# 261003902xxxx-HW-V1_1.net
KiCad netlist of a schematic drawn in EAGLE
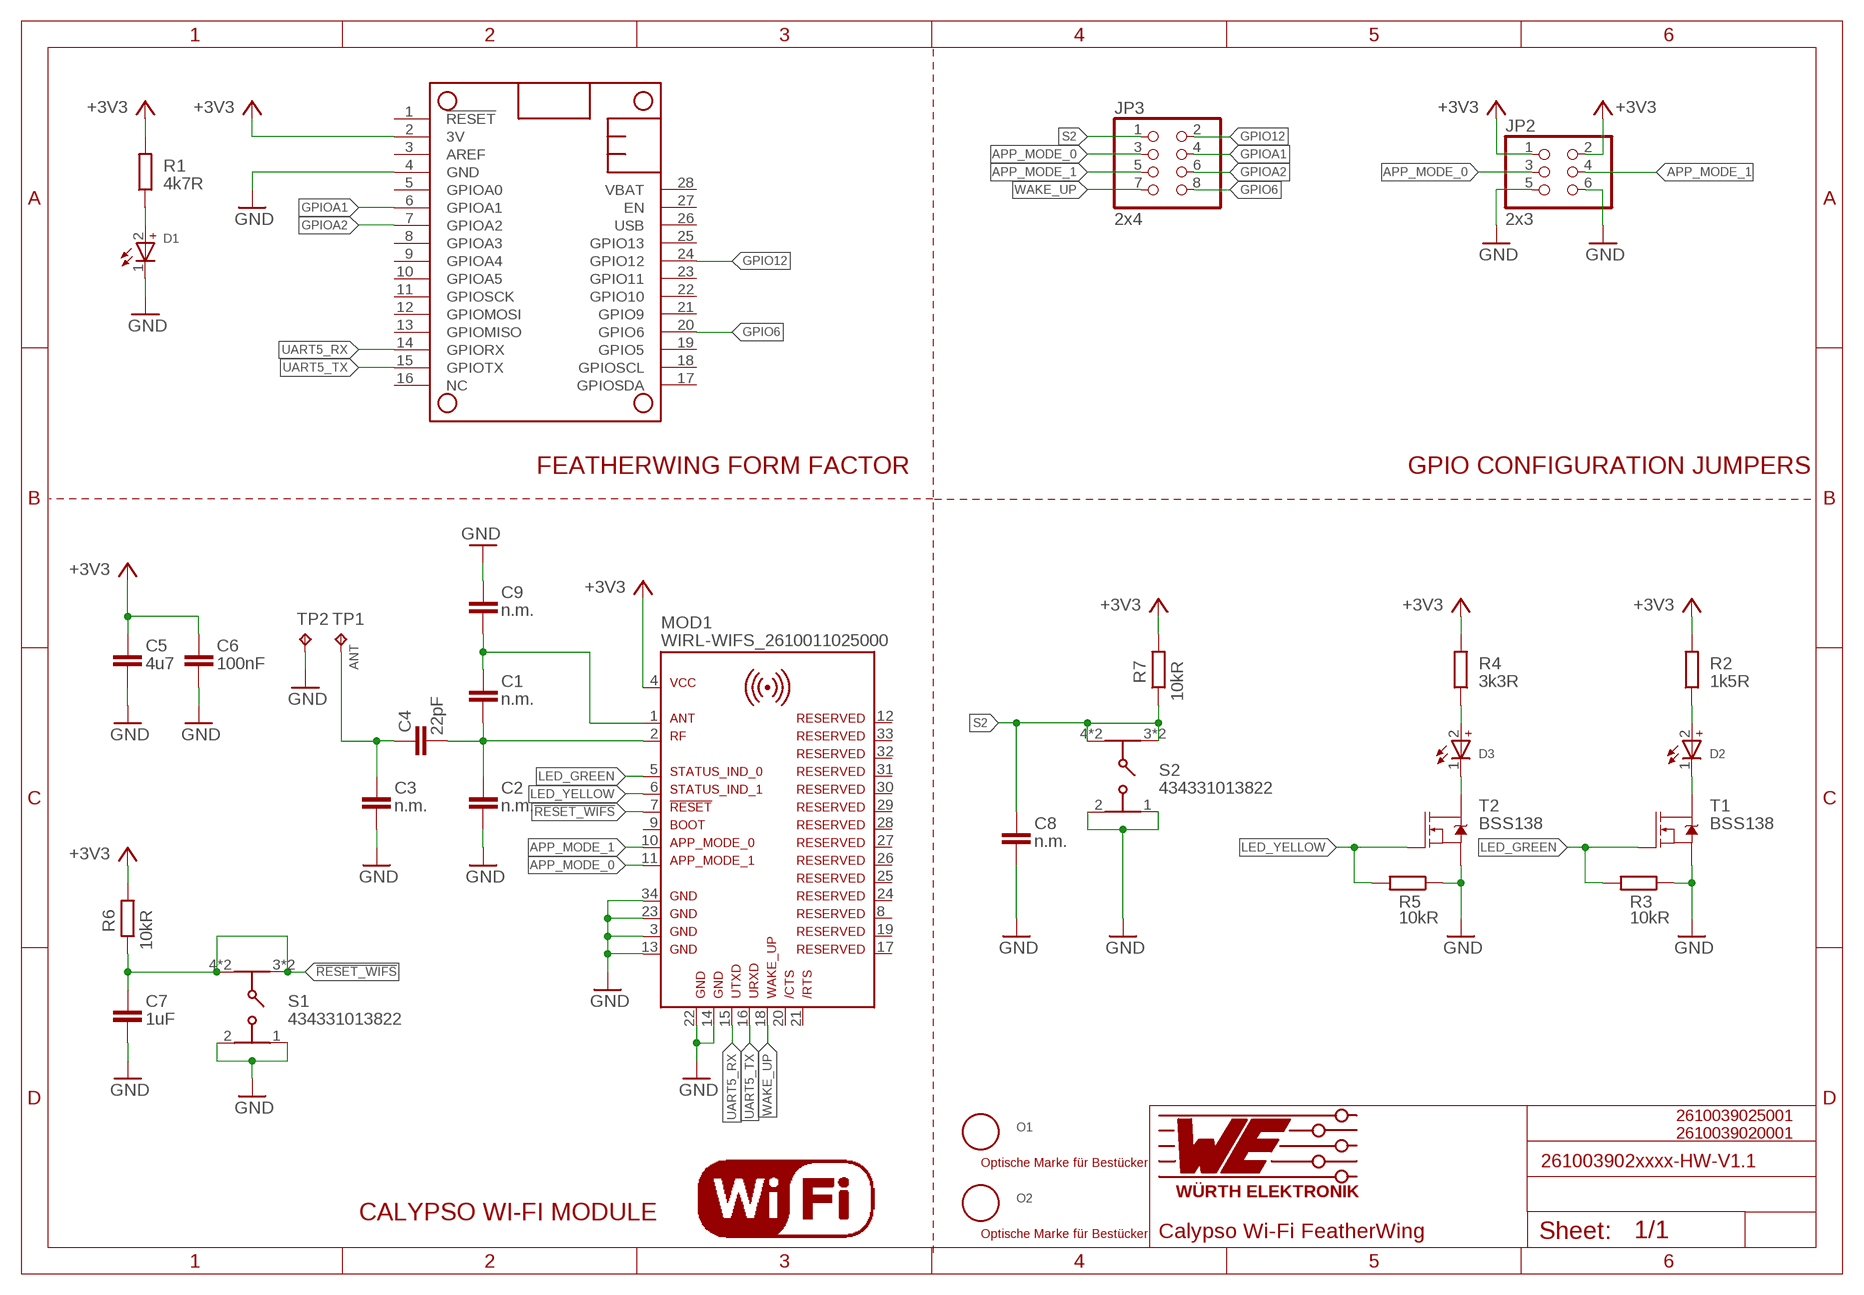
[diagram p0: schematic, sheet 1]

(export (version "E")
  (design (tool "Eeschema 10.0.6"))
  (components
    (comp (ref "C1")
      (value "n.m.")
      (footprint "eagle-import:C0402_IPC")
      (libsource (lib "eagle-import") (part "rcl-amber_C0402_IPC"))
    )
    (comp (ref "C2")
      (value "n.m.")
      (footprint "eagle-import:C0201_IPC")
      (libsource (lib "eagle-import") (part "rcl-amber_C0201_IPC"))
    )
    (comp (ref "C3")
      (value "n.m.")
      (footprint "eagle-import:C0201_IPC")
      (libsource (lib "eagle-import") (part "rcl-amber_C0201_IPC"))
    )
    (comp (ref "C4")
      (value "22pF")
      (footprint "eagle-import:C0402_IPC")
      (fields (field (name "MANUFACTURER") "Samsung"))
      (libsource (lib "eagle-import") (part "rcl-amber_C0402_IPC22PF"))
    )
    (comp (ref "C5")
      (value "4u7")
      (footprint "eagle-import:C0402_IPC")
      (fields (field (name "MANUFACTURER") "Würth Elektronik"))
      (libsource (lib "eagle-import") (part "C0402_IPC4.7UF"))
    )
    (comp (ref "C6")
      (value "100nF")
      (footprint "eagle-import:C0402_IPC")
      (fields (field (name "MANUFACTURER") "Yageo"))
      (libsource (lib "eagle-import") (part "rcl-amber_C0402_IPC100NF"))
    )
    (comp (ref "C7")
      (value "1uF")
      (footprint "eagle-import:C0402_IPC")
      (fields (field (name "MANUFACTURER") "Samsung"))
      (libsource (lib "eagle-import") (part "rcl-amber_C0402_IPC1UF"))
    )
    (comp (ref "C8")
      (value "n.m.")
      (footprint "eagle-import:C0402_IPC")
      (libsource (lib "eagle-import") (part "rcl-amber_C0402_IPC"))
    )
    (comp (ref "C9")
      (value "n.m.")
      (footprint "eagle-import:C0201_IPC")
      (libsource (lib "eagle-import") (part "rcl-amber_C0201_IPC"))
    )
    (comp (ref "D1")
      (value "RED")
      (footprint "eagle-import:WL-SMSW_1204_A")
      (fields (field (name "MANUFACTURER") "Würth Elektronik"))
      (libsource (lib "eagle-import") (part "WL-SMSW_1204_155124RS73200"))
    )
    (comp (ref "D2")
      (value "GREEN")
      (footprint "eagle-import:WL-SMSW_1204_A")
      (fields (field (name "MANUFACTURER") "Würth Elektronik"))
      (libsource (lib "eagle-import") (part "WL-SMSW_1204_155124VS73200"))
    )
    (comp (ref "D3")
      (value "YELLOW")
      (footprint "eagle-import:WL-SMSW_1204_A")
      (fields (field (name "MANUFACTURER") "Würth Elektronik"))
      (libsource (lib "eagle-import") (part "WL-SMSW_1204_155124YS73200"))
    )
    (comp (ref "JP2")
      (value "2x3")
      (footprint "eagle-import:2X03")
      (fields (field (name "MANUFACTURER") "Würth Elektronik"))
      (libsource (lib "eagle-import") (part "PINHD-2X3"))
    )
    (comp (ref "JP3")
      (value "2x4")
      (footprint "eagle-import:2X04")
      (fields (field (name "MANUFACTURER") "Würth Elektronik"))
      (libsource (lib "eagle-import") (part "PINHD-2X4"))
    )
    (comp (ref "MOD1")
      (value "WIRL-WIFS_2610011025000")
      (footprint "eagle-import:WIRL-WIFS_2610011025000")
      (fields (field (name "MANUFACTURER") "Würth Elektronik"))
      (libsource (lib "eagle-import") (part "WIRL-WIFS_2610011025000"))
    )
    (comp (ref "MS1")
      (value "header: 1 x 12 & 1 x 16")
      (footprint "eagle-import:FEATHERWING_80MM")
      (fields (field (name "COMMENT") "Kit containing 2 headers") (field (name "MANUFACTURER") "Adafruit"))
      (libsource (lib "eagle-import") (part "FEATHERWING_80MM"))
    )
    (comp (ref "O1")
      (value "n.m.")
      (footprint "eagle-import:OPTISCHE_MARKE")
      (libsource (lib "eagle-import") (part "OPT_MARKE"))
    )
    (comp (ref "O2")
      (value "n.m.")
      (footprint "eagle-import:OPTISCHE_MARKE")
      (libsource (lib "eagle-import") (part "OPT_MARKE"))
    )
    (comp (ref "R1")
      (value "4k7R")
      (footprint "eagle-import:R0402_IPC")
      (fields (field (name "MANUFACTURER") "Yageo"))
      (libsource (lib "eagle-import") (part "R0402_IPC4K7"))
    )
    (comp (ref "R2")
      (value "1k5R")
      (footprint "eagle-import:R0402_IPC")
      (fields (field (name "MANUFACTURER") "Yageo"))
      (libsource (lib "eagle-import") (part "R0402_IPC1K5R"))
    )
    (comp (ref "R3")
      (value "10kR")
      (footprint "eagle-import:R0402_IPC")
      (fields (field (name "MANUFACTURER") "Yageo"))
      (libsource (lib "eagle-import") (part "R0402_IPC10KR"))
    )
    (comp (ref "R4")
      (value "3k3R")
      (footprint "eagle-import:R0402_IPC")
      (fields (field (name "MANUFACTURER") "Yageo"))
      (libsource (lib "eagle-import") (part "R0402_IPC3K3R"))
    )
    (comp (ref "R5")
      (value "10kR")
      (footprint "eagle-import:R0402_IPC")
      (fields (field (name "MANUFACTURER") "Yageo"))
      (libsource (lib "eagle-import") (part "R0402_IPC10KR"))
    )
    (comp (ref "R6")
      (value "10kR")
      (footprint "eagle-import:R0402_IPC")
      (fields (field (name "MANUFACTURER") "Yageo"))
      (libsource (lib "eagle-import") (part "R0402_IPC10KR"))
    )
    (comp (ref "R7")
      (value "10kR")
      (footprint "eagle-import:R0402_IPC")
      (fields (field (name "MANUFACTURER") "Yageo"))
      (libsource (lib "eagle-import") (part "R0402_IPC10KR"))
    )
    (comp (ref "S1")
      (value "434331013822")
      (footprint "eagle-import:434331013822")
      (fields (field (name "MANUFACTURER") "Würth Elektronik"))
      (libsource (lib "eagle-import") (part "434331013822"))
    )
    (comp (ref "S2")
      (value "434331013822")
      (footprint "eagle-import:434331013822")
      (fields (field (name "MANUFACTURER") "Würth Elektronik"))
      (libsource (lib "eagle-import") (part "434331013822"))
    )
    (comp (ref "T1")
      (value "BSS138")
      (footprint "eagle-import:SOT23-3")
      (fields (field (name "MANUFACTURER") "Diodes Incorporated"))
      (libsource (lib "eagle-import") (part "MOSFET-NCH-BSS138"))
    )
    (comp (ref "T2")
      (value "BSS138")
      (footprint "eagle-import:SOT23-3")
      (fields (field (name "MANUFACTURER") "Diodes Incorporated"))
      (libsource (lib "eagle-import") (part "MOSFET-NCH-BSS138"))
    )
    (comp (ref "TP1")
      (value "n.m.")
      (footprint "eagle-import:D0.6")
      (libsource (lib "eagle-import") (part "TP-DRILL0.6"))
    )
    (comp (ref "TP2")
      (value "n.m.")
      (footprint "eagle-import:D0.6")
      (libsource (lib "eagle-import") (part "TP-DRILL0.6"))
    )
    (comp (ref "U$1")
      (value "WIFI5MM")
      (footprint "eagle-import:WIFI_5MM")
      (libsource (lib "eagle-import") (part "WIFI5MM"))
    )
  )
  (nets
    (net (code "1") (name "+3V3") (class "Default")
      (node (ref "C5") (pin "1") (pinfunction "1_1") (pintype "passive"))
      (node (ref "C6") (pin "1") (pinfunction "1_1") (pintype "passive"))
      (node (ref "JP2") (pin "1") (pinfunction "1_1") (pintype "passive"))
      (node (ref "JP2") (pin "2") (pinfunction "2_2") (pintype "passive"))
      (node (ref "MOD1") (pin "4") (pinfunction "4_4") (pintype "passive"))
      (node (ref "MS1") (pin "2") (pinfunction "3V_2") (pintype "power_in"))
      (node (ref "R1") (pin "2") (pinfunction "2_2") (pintype "passive"))
      (node (ref "R2") (pin "2") (pinfunction "2_2") (pintype "passive"))
      (node (ref "R4") (pin "2") (pinfunction "2_2") (pintype "passive"))
      (node (ref "R6") (pin "2") (pinfunction "2_2") (pintype "passive"))
      (node (ref "R7") (pin "2") (pinfunction "2_2") (pintype "passive"))
    )
    (net (code "2") (name "/ANT") (class "Default")
      (node (ref "C3") (pin "P$1") (pinfunction "1_P$1") (pintype "passive"))
      (node (ref "C4") (pin "1") (pinfunction "1_1") (pintype "passive"))
      (node (ref "TP1") (pin "P$1") (pinfunction "TP_P$1") (pintype "input"))
    )
    (net (code "3") (name "/USB") (class "Default")
      (node (ref "MS1") (pin "26") (pinfunction "USB_26") (pintype "power_in"))
    )
    (net (code "4") (name "/VBAT") (class "Default")
      (node (ref "MS1") (pin "28") (pinfunction "VBAT_28") (pintype "power_in"))
    )
    (net (code "5") (name "/~{RESET_WIFS}") (class "Default")
      (node (ref "C7") (pin "1") (pinfunction "1_1") (pintype "passive"))
      (node (ref "MOD1") (pin "7") (pinfunction "7_7") (pintype "input"))
      (node (ref "R6") (pin "1") (pinfunction "1_1") (pintype "passive"))
      (node (ref "S1") (pin "3") (pinfunction "3_3") (pintype "passive"))
      (node (ref "S1") (pin "4") (pinfunction "4_4") (pintype "passive"))
      (node (ref "S1") (pin "5") (pinfunction "3_5") (pintype "passive"))
      (node (ref "S1") (pin "6") (pinfunction "4_6") (pintype "passive"))
    )
    (net (code "6") (name "APP_MODE_0") (class "Default")
      (node (ref "JP2") (pin "3") (pinfunction "3_3") (pintype "passive"))
      (node (ref "JP3") (pin "3") (pinfunction "3_3") (pintype "passive"))
      (node (ref "MOD1") (pin "11") (pinfunction "11_11") (pintype "input"))
    )
    (net (code "7") (name "APP_MODE_1") (class "Default")
      (node (ref "JP2") (pin "4") (pinfunction "4_4") (pintype "passive"))
      (node (ref "JP3") (pin "5") (pinfunction "5_5") (pintype "passive"))
      (node (ref "MOD1") (pin "10") (pinfunction "10_10") (pintype "input"))
    )
    (net (code "8") (name "GND") (class "Default")
      (node (ref "C2") (pin "P$2") (pinfunction "2_P$2") (pintype "passive"))
      (node (ref "C3") (pin "P$2") (pinfunction "2_P$2") (pintype "passive"))
      (node (ref "C5") (pin "2") (pinfunction "2_2") (pintype "passive"))
      (node (ref "C6") (pin "2") (pinfunction "2_2") (pintype "passive"))
      (node (ref "C7") (pin "2") (pinfunction "2_2") (pintype "passive"))
      (node (ref "C8") (pin "2") (pinfunction "2_2") (pintype "passive"))
      (node (ref "C9") (pin "P$2") (pinfunction "2_P$2") (pintype "passive"))
      (node (ref "D1") (pin "1") (pinfunction "-_1") (pintype "passive"))
      (node (ref "JP2") (pin "5") (pinfunction "5_5") (pintype "passive"))
      (node (ref "JP2") (pin "6") (pinfunction "6_6") (pintype "passive"))
      (node (ref "MOD1") (pin "13") (pinfunction "13_13") (pintype "passive"))
      (node (ref "MOD1") (pin "14") (pinfunction "14_14") (pintype "passive"))
      (node (ref "MOD1") (pin "22") (pinfunction "22_22") (pintype "passive"))
      (node (ref "MOD1") (pin "23") (pinfunction "23_23") (pintype "passive"))
      (node (ref "MOD1") (pin "3") (pinfunction "3_3") (pintype "passive"))
      (node (ref "MOD1") (pin "34") (pinfunction "34_34") (pintype "passive"))
      (node (ref "MS1") (pin "4") (pinfunction "GND_4") (pintype "power_in"))
      (node (ref "R3") (pin "1") (pinfunction "1_1") (pintype "passive"))
      (node (ref "R5") (pin "1") (pinfunction "1_1") (pintype "passive"))
      (node (ref "S1") (pin "1") (pinfunction "1_1") (pintype "passive"))
      (node (ref "S1") (pin "2") (pinfunction "2_2") (pintype "passive"))
      (node (ref "S2") (pin "1") (pinfunction "1_1") (pintype "passive"))
      (node (ref "S2") (pin "2") (pinfunction "2_2") (pintype "passive"))
      (node (ref "T1") (pin "2") (pinfunction "S_2") (pintype "bidirectional"))
      (node (ref "T2") (pin "2") (pinfunction "S_2") (pintype "bidirectional"))
      (node (ref "TP2") (pin "P$1") (pinfunction "TP_P$1") (pintype "input"))
    )
    (net (code "9") (name "GPIO6") (class "Default")
      (node (ref "JP3") (pin "8") (pinfunction "8_8") (pintype "passive"))
      (node (ref "MS1") (pin "20") (pinfunction "GPIO6_20") (pintype "bidirectional"))
    )
    (net (code "10") (name "GPIO12") (class "Default")
      (node (ref "JP3") (pin "2") (pinfunction "2_2") (pintype "passive"))
      (node (ref "MS1") (pin "24") (pinfunction "GPIO12_24") (pintype "bidirectional"))
    )
    (net (code "11") (name "GPIOA1") (class "Default")
      (node (ref "JP3") (pin "4") (pinfunction "4_4") (pintype "passive"))
      (node (ref "MS1") (pin "6") (pinfunction "GPIOA1_6") (pintype "bidirectional"))
    )
    (net (code "12") (name "GPIOA2") (class "Default")
      (node (ref "JP3") (pin "6") (pinfunction "6_6") (pintype "passive"))
      (node (ref "MS1") (pin "7") (pinfunction "GPIOA2_7") (pintype "bidirectional"))
    )
    (net (code "13") (name "LED_GREEN") (class "Default")
      (node (ref "MOD1") (pin "5") (pinfunction "5_5") (pintype "output"))
      (node (ref "R3") (pin "2") (pinfunction "2_2") (pintype "passive"))
      (node (ref "T1") (pin "1") (pinfunction "G_1") (pintype "bidirectional"))
    )
    (net (code "14") (name "LED_YELLOW") (class "Default")
      (node (ref "MOD1") (pin "6") (pinfunction "6_6") (pintype "output"))
      (node (ref "R5") (pin "2") (pinfunction "2_2") (pintype "passive"))
      (node (ref "T2") (pin "1") (pinfunction "G_1") (pintype "bidirectional"))
    )
    (net (code "15") (name "Net-(C2-1)") (class "Default")
      (node (ref "C1") (pin "1") (pinfunction "1_1") (pintype "passive"))
      (node (ref "C2") (pin "P$1") (pinfunction "1_P$1") (pintype "passive"))
      (node (ref "C4") (pin "2") (pinfunction "2_2") (pintype "passive"))
      (node (ref "MOD1") (pin "2") (pinfunction "2_2") (pintype "passive"))
    )
    (net (code "16") (name "Net-(C9-1)") (class "Default")
      (node (ref "C1") (pin "2") (pinfunction "2_2") (pintype "passive"))
      (node (ref "C9") (pin "P$1") (pinfunction "1_P$1") (pintype "passive"))
      (node (ref "MOD1") (pin "1") (pinfunction "1_1") (pintype "passive"))
    )
    (net (code "17") (name "Net-(D1-+)") (class "Default")
      (node (ref "D1") (pin "2") (pinfunction "+_2") (pintype "passive"))
      (node (ref "R1") (pin "1") (pinfunction "1_1") (pintype "passive"))
    )
    (net (code "18") (name "Net-(D2-+)") (class "Default")
      (node (ref "D2") (pin "2") (pinfunction "+_2") (pintype "passive"))
      (node (ref "R2") (pin "1") (pinfunction "1_1") (pintype "passive"))
    )
    (net (code "19") (name "Net-(D2--)") (class "Default")
      (node (ref "D2") (pin "1") (pinfunction "-_1") (pintype "passive"))
      (node (ref "T1") (pin "3") (pinfunction "D_3") (pintype "bidirectional"))
    )
    (net (code "20") (name "Net-(D3-+)") (class "Default")
      (node (ref "D3") (pin "2") (pinfunction "+_2") (pintype "passive"))
      (node (ref "R4") (pin "1") (pinfunction "1_1") (pintype "passive"))
    )
    (net (code "21") (name "Net-(D3--)") (class "Default")
      (node (ref "D3") (pin "1") (pinfunction "-_1") (pintype "passive"))
      (node (ref "T2") (pin "3") (pinfunction "D_3") (pintype "bidirectional"))
    )
    (net (code "22") (name "S2") (class "Default")
      (node (ref "C8") (pin "1") (pinfunction "1_1") (pintype "passive"))
      (node (ref "JP3") (pin "1") (pinfunction "1_1") (pintype "passive"))
      (node (ref "R7") (pin "1") (pinfunction "1_1") (pintype "passive"))
      (node (ref "S2") (pin "3") (pinfunction "3_3") (pintype "passive"))
      (node (ref "S2") (pin "4") (pinfunction "4_4") (pintype "passive"))
      (node (ref "S2") (pin "5") (pinfunction "3_5") (pintype "passive"))
      (node (ref "S2") (pin "6") (pinfunction "4_6") (pintype "passive"))
    )
    (net (code "23") (name "UART5_RX") (class "Default")
      (node (ref "MOD1") (pin "15") (pinfunction "15_15") (pintype "output"))
      (node (ref "MS1") (pin "14") (pinfunction "GPIORX_14") (pintype "bidirectional"))
    )
    (net (code "24") (name "UART5_TX") (class "Default")
      (node (ref "MOD1") (pin "16") (pinfunction "16_16") (pintype "input"))
      (node (ref "MS1") (pin "15") (pinfunction "GPIOTX_15") (pintype "bidirectional"))
    )
    (net (code "25") (name "WAKE_UP") (class "Default")
      (node (ref "JP3") (pin "7") (pinfunction "7_7") (pintype "passive"))
      (node (ref "MOD1") (pin "18") (pinfunction "18_18") (pintype "input"))
    )
    (net (code "26") (name "unconnected-(MOD1-Pad8)") (class "Default")
      (node (ref "MOD1") (pin "8") (pinfunction "8_8") (pintype "passive"))
    )
    (net (code "27") (name "unconnected-(MOD1-Pad9)") (class "Default")
      (node (ref "MOD1") (pin "9") (pinfunction "9_9") (pintype "input"))
    )
    (net (code "28") (name "unconnected-(MOD1-Pad12)") (class "Default")
      (node (ref "MOD1") (pin "12") (pinfunction "12_12") (pintype "passive"))
    )
    (net (code "29") (name "unconnected-(MOD1-Pad17)") (class "Default")
      (node (ref "MOD1") (pin "17") (pinfunction "17_17") (pintype "passive"))
    )
    (net (code "30") (name "unconnected-(MOD1-Pad19)") (class "Default")
      (node (ref "MOD1") (pin "19") (pinfunction "19_19") (pintype "passive"))
    )
    (net (code "31") (name "unconnected-(MOD1-Pad20)") (class "Default")
      (node (ref "MOD1") (pin "20") (pinfunction "20_20") (pintype "input"))
    )
    (net (code "32") (name "unconnected-(MOD1-Pad21)") (class "Default")
      (node (ref "MOD1") (pin "21") (pinfunction "21_21") (pintype "output"))
    )
    (net (code "33") (name "unconnected-(MOD1-Pad24)") (class "Default")
      (node (ref "MOD1") (pin "24") (pinfunction "24_24") (pintype "passive"))
    )
    (net (code "34") (name "unconnected-(MOD1-Pad25)") (class "Default")
      (node (ref "MOD1") (pin "25") (pinfunction "25_25") (pintype "passive"))
    )
    (net (code "35") (name "unconnected-(MOD1-Pad26)") (class "Default")
      (node (ref "MOD1") (pin "26") (pinfunction "26_26") (pintype "passive"))
    )
    (net (code "36") (name "unconnected-(MOD1-Pad27)") (class "Default")
      (node (ref "MOD1") (pin "27") (pinfunction "27_27") (pintype "passive"))
    )
    (net (code "37") (name "unconnected-(MOD1-Pad28)") (class "Default")
      (node (ref "MOD1") (pin "28") (pinfunction "28_28") (pintype "passive"))
    )
    (net (code "38") (name "unconnected-(MOD1-Pad29)") (class "Default")
      (node (ref "MOD1") (pin "29") (pinfunction "29_29") (pintype "passive"))
    )
    (net (code "39") (name "unconnected-(MOD1-Pad30)") (class "Default")
      (node (ref "MOD1") (pin "30") (pinfunction "30_30") (pintype "passive"))
    )
    (net (code "40") (name "unconnected-(MOD1-Pad31)") (class "Default")
      (node (ref "MOD1") (pin "31") (pinfunction "31_31") (pintype "passive"))
    )
    (net (code "41") (name "unconnected-(MOD1-Pad32)") (class "Default")
      (node (ref "MOD1") (pin "32") (pinfunction "32_32") (pintype "passive"))
    )
    (net (code "42") (name "unconnected-(MOD1-Pad33)") (class "Default")
      (node (ref "MOD1") (pin "33") (pinfunction "33_33") (pintype "passive"))
    )
    (net (code "43") (name "unconnected-(MS1-AREF-Pad3)") (class "Default")
      (node (ref "MS1") (pin "3") (pinfunction "AREF_3") (pintype "passive"))
    )
    (net (code "44") (name "unconnected-(MS1-EN-Pad27)") (class "Default")
      (node (ref "MS1") (pin "27") (pinfunction "EN_27") (pintype "passive"))
    )
    (net (code "45") (name "unconnected-(MS1-GPIO5-Pad19)") (class "Default")
      (node (ref "MS1") (pin "19") (pinfunction "GPIO5_19") (pintype "bidirectional"))
    )
    (net (code "46") (name "unconnected-(MS1-GPIO9-Pad21)") (class "Default")
      (node (ref "MS1") (pin "21") (pinfunction "GPIO9_21") (pintype "bidirectional"))
    )
    (net (code "47") (name "unconnected-(MS1-GPIO10-Pad22)") (class "Default")
      (node (ref "MS1") (pin "22") (pinfunction "GPIO10_22") (pintype "bidirectional"))
    )
    (net (code "48") (name "unconnected-(MS1-GPIO11-Pad23)") (class "Default")
      (node (ref "MS1") (pin "23") (pinfunction "GPIO11_23") (pintype "bidirectional"))
    )
    (net (code "49") (name "unconnected-(MS1-GPIO13-Pad25)") (class "Default")
      (node (ref "MS1") (pin "25") (pinfunction "GPIO13_25") (pintype "bidirectional"))
    )
    (net (code "50") (name "unconnected-(MS1-GPIOA0-Pad5)") (class "Default")
      (node (ref "MS1") (pin "5") (pinfunction "GPIOA0_5") (pintype "bidirectional"))
    )
    (net (code "51") (name "unconnected-(MS1-GPIOA3-Pad8)") (class "Default")
      (node (ref "MS1") (pin "8") (pinfunction "GPIOA3_8") (pintype "bidirectional"))
    )
    (net (code "52") (name "unconnected-(MS1-GPIOA4-Pad9)") (class "Default")
      (node (ref "MS1") (pin "9") (pinfunction "GPIOA4_9") (pintype "bidirectional"))
    )
    (net (code "53") (name "unconnected-(MS1-GPIOA5-Pad10)") (class "Default")
      (node (ref "MS1") (pin "10") (pinfunction "GPIOA5_10") (pintype "bidirectional"))
    )
    (net (code "54") (name "unconnected-(MS1-GPIOMISO-Pad13)") (class "Default")
      (node (ref "MS1") (pin "13") (pinfunction "GPIOMISO_13") (pintype "bidirectional"))
    )
    (net (code "55") (name "unconnected-(MS1-GPIOMOSI-Pad12)") (class "Default")
      (node (ref "MS1") (pin "12") (pinfunction "GPIOMOSI_12") (pintype "bidirectional"))
    )
    (net (code "56") (name "unconnected-(MS1-GPIOSCK-Pad11)") (class "Default")
      (node (ref "MS1") (pin "11") (pinfunction "GPIOSCK_11") (pintype "bidirectional"))
    )
    (net (code "57") (name "unconnected-(MS1-GPIOSCL-Pad18)") (class "Default")
      (node (ref "MS1") (pin "18") (pinfunction "GPIOSCL_18") (pintype "bidirectional"))
    )
    (net (code "58") (name "unconnected-(MS1-GPIOSDA-Pad17)") (class "Default")
      (node (ref "MS1") (pin "17") (pinfunction "GPIOSDA_17") (pintype "bidirectional"))
    )
    (net (code "59") (name "unconnected-(MS1-NC-Pad16)") (class "Default")
      (node (ref "MS1") (pin "16") (pinfunction "NC_16") (pintype "passive"))
    )
    (net (code "60") (name "unconnected-(MS1-~{RESET}-Pad1)") (class "Default")
      (node (ref "MS1") (pin "1") (pinfunction "~{RESET}_1") (pintype "input"))
    )
  )
)
